# STM32CC.net
KiCad netlist of a schematic drawn in Altium Designer
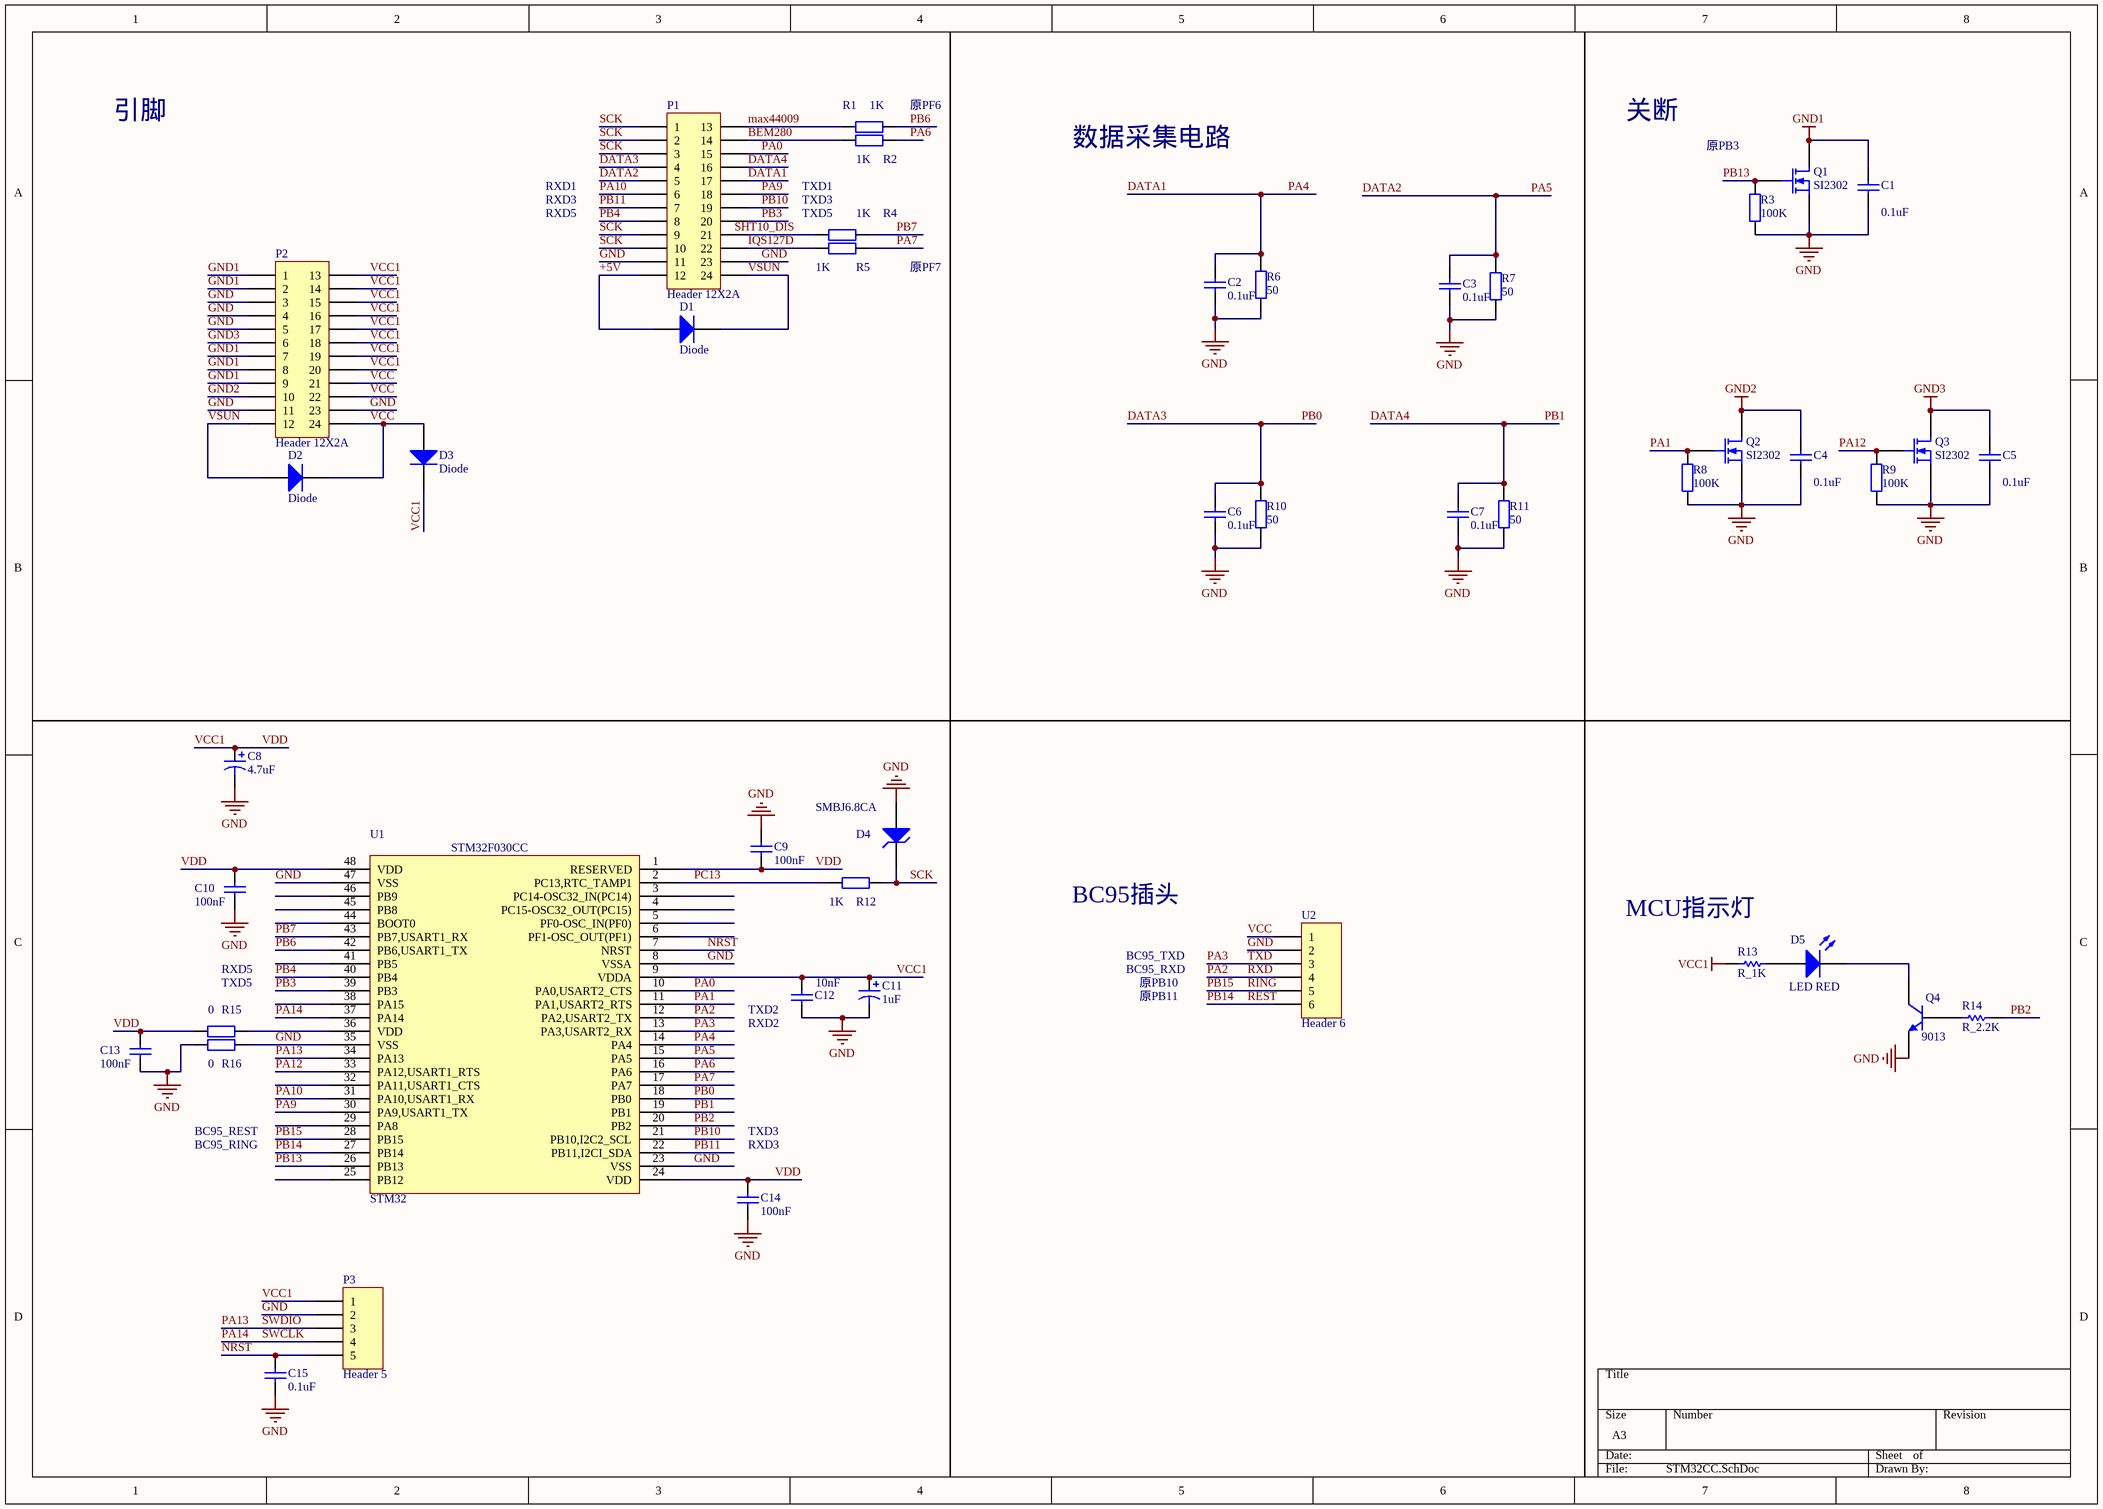
[diagram p0: STM32CC.SchDoc]

(export (version "E")
  (design (tool "Eeschema 10.0.6"))
  (components
    (comp (ref "C1")
      (value "0.1uF")
      (footprint "0603")
      (description "Capacitor")
      (fields (field (name "Comment") "Cap") (field (name "PUBLISHER") "Altium Limited"))
      (libsource (lib "Miscellaneous Devices") (part "Cap"))
    )
    (comp (ref "C2")
      (value "0.1uF")
      (footprint "0603")
      (description "贴片电容 0603")
      (fields (field (name "Comment") "C_0.1uF") (field (name "PUBLISHER") "Altium Limited"))
      (libsource (lib "Miscellaneous Devices") (part "Cap"))
    )
    (comp (ref "C3")
      (value "0.1uF")
      (footprint "0603")
      (description "贴片电容 0603")
      (fields (field (name "Comment") "C_0.1uF") (field (name "PUBLISHER") "Altium Limited"))
      (libsource (lib "Miscellaneous Devices") (part "Cap"))
    )
    (comp (ref "C4")
      (value "0.1uF")
      (footprint "0603")
      (description "Capacitor")
      (fields (field (name "Comment") "Cap") (field (name "PUBLISHER") "Altium Limited"))
      (libsource (lib "Miscellaneous Devices") (part "Cap"))
    )
    (comp (ref "C5")
      (value "0.1uF")
      (footprint "0603")
      (description "Capacitor")
      (fields (field (name "Comment") "Cap") (field (name "PUBLISHER") "Altium Limited"))
      (libsource (lib "Miscellaneous Devices") (part "Cap"))
    )
    (comp (ref "C6")
      (value "0.1uF")
      (footprint "0603")
      (description "贴片电容 0603")
      (fields (field (name "Comment") "C_0.1uF") (field (name "PUBLISHER") "Altium Limited"))
      (libsource (lib "Miscellaneous Devices") (part "Cap"))
    )
    (comp (ref "C7")
      (value "0.1uF")
      (footprint "0603")
      (description "贴片电容 0603")
      (fields (field (name "Comment") "C_0.1uF") (field (name "PUBLISHER") "Altium Limited"))
      (libsource (lib "Miscellaneous Devices") (part "Cap"))
    )
    (comp (ref "C8")
      (value "4.7uF")
      (footprint "1206")
      (description "Polarized Capacitor (Radial)")
      (fields (field (name "PUBLISHER") "Altium Limited"))
      (libsource (lib "Miscellaneous Devices") (part "Cap Pol1"))
    )
    (comp (ref "C9")
      (value "100nF")
      (footprint "0603")
      (description "Capacitor")
      (fields (field (name "PUBLISHER") "Altium Limited"))
      (libsource (lib "Miscellaneous Devices") (part "Cap"))
    )
    (comp (ref "C10")
      (value "100nF")
      (footprint "0603")
      (description "Capacitor")
      (fields (field (name "PUBLISHER") "Altium Limited"))
      (libsource (lib "Miscellaneous Devices") (part "Cap"))
    )
    (comp (ref "C11")
      (value "1uF")
      (footprint "1206")
      (description "Polarized Capacitor (Radial)")
      (fields (field (name "PUBLISHER") "Altium Limited"))
      (libsource (lib "Miscellaneous Devices") (part "Cap Pol1"))
    )
    (comp (ref "C12")
      (value "10nF")
      (footprint "0603")
      (description "Capacitor")
      (fields (field (name "PUBLISHER") "Altium Limited"))
      (libsource (lib "Miscellaneous Devices") (part "Cap"))
    )
    (comp (ref "C13")
      (value "100nF")
      (footprint "0603")
      (description "Capacitor")
      (fields (field (name "PUBLISHER") "Altium Limited"))
      (libsource (lib "Miscellaneous Devices") (part "Cap"))
    )
    (comp (ref "C14")
      (value "100nF")
      (footprint "0603")
      (description "Capacitor")
      (fields (field (name "PUBLISHER") "Altium Limited"))
      (libsource (lib "Miscellaneous Devices") (part "Cap"))
    )
    (comp (ref "C15")
      (value "0.1uF")
      (footprint "0603")
      (description "Capacitor")
      (fields (field (name "PUBLISHER") "Altium Limited"))
      (libsource (lib "Miscellaneous Devices") (part "Cap"))
    )
    (comp (ref "D1")
      (value "Diode")
      (footprint "1N4007-M7")
      (description "Default Diode")
      (fields (field (name "PUBLISHER") "Altium Limited"))
      (libsource (lib "Miscellaneous Devices") (part "Diode"))
    )
    (comp (ref "D2")
      (value "Diode")
      (footprint "1N4007-M7")
      (description "Default Diode")
      (fields (field (name "PUBLISHER") "Altium Limited"))
      (libsource (lib "Miscellaneous Devices") (part "Diode"))
    )
    (comp (ref "D3")
      (value "Diode")
      (footprint "1N4007-M7")
      (description "Default Diode")
      (fields (field (name "PUBLISHER") "Altium Limited"))
      (libsource (lib "Miscellaneous Devices") (part "Diode"))
    )
    (comp (ref "D4")
      (value "SMBJ6.8CA")
      (footprint "DO-214AB")
      (description "Zener Diode")
      (fields (field (name "PUBLISHER") "Altium Limited"))
      (libsource (lib "Miscellaneous Devices") (part "D Zener"))
    )
    (comp (ref "D5")
      (value "LED RED")
      (footprint "LED-3mm")
      (description "插件 发光二极管 5mm 绿发绿光")
      (fields (field (name "PUBLISHER") "Altium Limited"))
      (libsource (lib "Miscellaneous Devices") (part "LED0"))
    )
    (comp (ref "P1")
      (value "Header 12X2A")
      (footprint "HDR2X12_CEN")
      (description "Header, 12-Pin, Dual row")
      (fields (field (name "PUBLISHER") "Altium Limited"))
      (libsource (lib "Miscellaneous Connectors") (part "Header 12X2A"))
    )
    (comp (ref "P2")
      (value "Header 12X2A")
      (footprint "HDR2X12_CEN")
      (description "Header, 12-Pin, Dual row")
      (fields (field (name "PUBLISHER") "Altium Limited"))
      (libsource (lib "Miscellaneous Connectors") (part "Header 12X2A"))
    )
    (comp (ref "P3")
      (value "Header 5")
      (footprint "HDR1X5")
      (description "Header, 5-Pin")
      (fields (field (name "PUBLISHER") "Altium Limited"))
      (libsource (lib "Miscellaneous Connectors") (part "Header 5"))
    )
    (comp (ref "Q1")
      (value "SI2302")
      (footprint "SOT23-3")
      (description "N-Channel MOSFET")
      (fields (field (name "PUBLISHER") "Altium Limited"))
      (libsource (lib "SCHLIB") (part "MOSFET-N"))
    )
    (comp (ref "Q2")
      (value "SI2302")
      (footprint "SOT23-3")
      (description "N-Channel MOSFET")
      (fields (field (name "PUBLISHER") "Altium Limited"))
      (libsource (lib "SCHLIB") (part "MOSFET-N"))
    )
    (comp (ref "Q3")
      (value "SI2302")
      (footprint "SOT23-3")
      (description "N-Channel MOSFET")
      (fields (field (name "PUBLISHER") "Altium Limited"))
      (libsource (lib "SCHLIB") (part "MOSFET-N"))
    )
    (comp (ref "Q4")
      (value "9013")
      (footprint "SOT-23")
      (description "贴片三极管MMBT5551 SOT-23")
      (fields (field (name "PUBLISHER") "Altium Limited"))
      (libsource (lib "MyMiscellaneousDevices") (part "NPN"))
    )
    (comp (ref "R1")
      (value "1K")
      (footprint "0603")
      (description "Resistor")
      (fields (field (name "PUBLISHER") "Altium Limited"))
      (libsource (lib "Miscellaneous Devices") (part "Res2"))
    )
    (comp (ref "R2")
      (value "1K")
      (footprint "0603")
      (description "Resistor")
      (fields (field (name "PUBLISHER") "Altium Limited"))
      (libsource (lib "Miscellaneous Devices") (part "Res2"))
    )
    (comp (ref "R3")
      (value "100K")
      (footprint "0603")
      (description "Resistor")
      (fields (field (name "PUBLISHER") "Altium Limited"))
      (libsource (lib "") (part "Res2_1"))
    )
    (comp (ref "R4")
      (value "1K")
      (footprint "0603")
      (description "Resistor")
      (fields (field (name "PUBLISHER") "Altium Limited"))
      (libsource (lib "Miscellaneous Devices") (part "Res2"))
    )
    (comp (ref "R5")
      (value "1K")
      (footprint "0603")
      (description "Resistor")
      (fields (field (name "PUBLISHER") "Altium Limited"))
      (libsource (lib "Miscellaneous Devices") (part "Res2"))
    )
    (comp (ref "R6")
      (value "50")
      (footprint "0805")
      (description "贴片电阻 0805 精度0.1%")
      (fields (field (name "Comment") "50R") (field (name "PUBLISHER") "Altium Limited"))
      (libsource (lib "") (part "Res2_1"))
    )
    (comp (ref "R7")
      (value "50")
      (footprint "0805")
      (description "贴片电阻 0805 精度0.1%")
      (fields (field (name "Comment") "50R") (field (name "PUBLISHER") "Altium Limited"))
      (libsource (lib "") (part "Res2_1"))
    )
    (comp (ref "R8")
      (value "100K")
      (footprint "0603")
      (description "Resistor")
      (fields (field (name "PUBLISHER") "Altium Limited"))
      (libsource (lib "") (part "Res2_1"))
    )
    (comp (ref "R9")
      (value "100K")
      (footprint "0603")
      (description "Resistor")
      (fields (field (name "PUBLISHER") "Altium Limited"))
      (libsource (lib "") (part "Res2_1"))
    )
    (comp (ref "R10")
      (value "50")
      (footprint "0805")
      (description "贴片电阻 0805 精度0.1%")
      (fields (field (name "Comment") "50R") (field (name "PUBLISHER") "Altium Limited"))
      (libsource (lib "") (part "Res2_1"))
    )
    (comp (ref "R11")
      (value "50")
      (footprint "0805")
      (description "贴片电阻 0805 精度0.1%")
      (fields (field (name "Comment") "50R") (field (name "PUBLISHER") "Altium Limited"))
      (libsource (lib "") (part "Res2_1"))
    )
    (comp (ref "R12")
      (value "1K")
      (footprint "0603")
      (description "Resistor")
      (fields (field (name "PUBLISHER") "Altium Limited"))
      (libsource (lib "Miscellaneous Devices") (part "Res2"))
    )
    (comp (ref "R13")
      (value "R_1K")
      (footprint "0603")
      (description "Resistor")
      (libsource (lib "MyMiscellaneousDevices") (part "Resistor"))
    )
    (comp (ref "R14")
      (value "R_2.2K")
      (footprint "0603")
      (description "Resistor")
      (libsource (lib "MyMiscellaneousDevices") (part "Resistor"))
    )
    (comp (ref "R15")
      (value "0")
      (footprint "0603")
      (description "Resistor")
      (fields (field (name "PUBLISHER") "Altium Limited"))
      (libsource (lib "Miscellaneous Devices") (part "Res2"))
    )
    (comp (ref "R16")
      (value "0")
      (footprint "0603")
      (description "Resistor")
      (fields (field (name "PUBLISHER") "Altium Limited"))
      (libsource (lib "Miscellaneous Devices") (part "Res2"))
    )
    (comp (ref "U1") (value "STM32") (footprint "LQFP48_N") (libsource (lib "STM32F030CC") (part "STM32")))
    (comp (ref "U2")
      (value "Header 6")
      (footprint "PCBComponent_1")
      (description "Header, 6-Pin")
      (fields (field (name "PUBLISHER") "Altium Limited"))
      (libsource (lib "Miscellaneous Connectors") (part "Header 6"))
    )
  )
  (nets
    (net (code "1") (name "/+5V") (class "Default")
      (node (ref "D1") (pin "1") (pinfunction "A_1") (pintype "passive"))
      (node (ref "P1") (pin "12") (pinfunction "12_12") (pintype "passive"))
    )
    (net (code "2") (name "/BEM280") (class "Default")
      (node (ref "P1") (pin "14") (pinfunction "14_14") (pintype "passive"))
      (node (ref "R2") (pin "1") (pinfunction "1_1") (pintype "passive"))
    )
    (net (code "3") (name "/DATA1") (class "Default")
      (node (ref "C2") (pin "1") (pinfunction "1_1") (pintype "passive"))
      (node (ref "P1") (pin "17") (pinfunction "17_17") (pintype "passive"))
      (node (ref "R6") (pin "2") (pinfunction "2_2") (pintype "passive"))
      (node (ref "U1") (pin "14") (pinfunction "PA4_14") (pintype "passive"))
    )
    (net (code "4") (name "/DATA2") (class "Default")
      (node (ref "C3") (pin "1") (pinfunction "1_1") (pintype "passive"))
      (node (ref "P1") (pin "5") (pinfunction "5_5") (pintype "passive"))
      (node (ref "R7") (pin "2") (pinfunction "2_2") (pintype "passive"))
      (node (ref "U1") (pin "15") (pinfunction "PA5_15") (pintype "passive"))
    )
    (net (code "5") (name "/DATA3") (class "Default")
      (node (ref "C6") (pin "1") (pinfunction "1_1") (pintype "passive"))
      (node (ref "P1") (pin "4") (pinfunction "4_4") (pintype "passive"))
      (node (ref "R10") (pin "2") (pinfunction "2_2") (pintype "passive"))
      (node (ref "U1") (pin "18") (pinfunction "PB0_18") (pintype "passive"))
    )
    (net (code "6") (name "/DATA4") (class "Default")
      (node (ref "C7") (pin "1") (pinfunction "1_1") (pintype "passive"))
      (node (ref "P1") (pin "16") (pinfunction "16_16") (pintype "passive"))
      (node (ref "R11") (pin "2") (pinfunction "2_2") (pintype "passive"))
      (node (ref "U1") (pin "19") (pinfunction "PB1_19") (pintype "passive"))
    )
    (net (code "7") (name "/IQS127D") (class "Default")
      (node (ref "P1") (pin "22") (pinfunction "22_22") (pintype "passive"))
      (node (ref "R5") (pin "1") (pinfunction "1_1") (pintype "passive"))
    )
    (net (code "8") (name "/NRST") (class "Default")
      (node (ref "C15") (pin "1") (pinfunction "1_1") (pintype "passive"))
      (node (ref "P3") (pin "5") (pinfunction "5_5") (pintype "passive"))
      (node (ref "U1") (pin "7") (pinfunction "NRST_7") (pintype "passive"))
    )
    (net (code "9") (name "/PA0") (class "Default")
      (node (ref "P1") (pin "15") (pinfunction "15_15") (pintype "passive"))
      (node (ref "U1") (pin "10") (pinfunction "PA0,USART2_CTS_10") (pintype "passive"))
    )
    (net (code "10") (name "/PA1") (class "Default")
      (node (ref "Q2") (pin "1") (pinfunction "G_1") (pintype "passive"))
      (node (ref "R8") (pin "2") (pinfunction "2_2") (pintype "passive"))
      (node (ref "U1") (pin "11") (pinfunction "PA1,USART2_RTS_11") (pintype "passive"))
    )
    (net (code "11") (name "/PA2") (class "Default")
      (node (ref "U1") (pin "12") (pinfunction "PA2,USART2_TX_12") (pintype "passive"))
      (node (ref "U2") (pin "4") (pinfunction "4_4") (pintype "passive"))
    )
    (net (code "12") (name "/PA3") (class "Default")
      (node (ref "U1") (pin "13") (pinfunction "PA3,USART2_RX_13") (pintype "passive"))
      (node (ref "U2") (pin "3") (pinfunction "3_3") (pintype "passive"))
    )
    (net (code "13") (name "/PA6") (class "Default")
      (node (ref "R2") (pin "2") (pinfunction "2_2") (pintype "passive"))
      (node (ref "U1") (pin "16") (pinfunction "PA6_16") (pintype "passive"))
    )
    (net (code "14") (name "/PA7") (class "Default")
      (node (ref "R5") (pin "2") (pinfunction "2_2") (pintype "passive"))
      (node (ref "U1") (pin "17") (pinfunction "PA7_17") (pintype "passive"))
    )
    (net (code "15") (name "/PA9") (class "Default")
      (node (ref "P1") (pin "18") (pinfunction "18_18") (pintype "passive"))
      (node (ref "U1") (pin "30") (pinfunction "PA9,USART1_TX_30") (pintype "passive"))
    )
    (net (code "16") (name "/PA10") (class "Default")
      (node (ref "P1") (pin "6") (pinfunction "6_6") (pintype "passive"))
      (node (ref "U1") (pin "31") (pinfunction "PA10,USART1_RX_31") (pintype "passive"))
    )
    (net (code "17") (name "/PA12") (class "Default")
      (node (ref "Q3") (pin "1") (pinfunction "G_1") (pintype "passive"))
      (node (ref "R9") (pin "2") (pinfunction "2_2") (pintype "passive"))
      (node (ref "U1") (pin "33") (pinfunction "PA12,USART1_RTS_33") (pintype "passive"))
    )
    (net (code "18") (name "/PA13") (class "Default")
      (node (ref "P3") (pin "3") (pinfunction "3_3") (pintype "passive"))
      (node (ref "U1") (pin "34") (pinfunction "PA13_34") (pintype "passive"))
    )
    (net (code "19") (name "/PA14") (class "Default")
      (node (ref "P3") (pin "4") (pinfunction "4_4") (pintype "passive"))
      (node (ref "U1") (pin "37") (pinfunction "PA14_37") (pintype "passive"))
    )
    (net (code "20") (name "/PB2") (class "Default")
      (node (ref "R14") (pin "2") (pinfunction "2_2") (pintype "passive"))
      (node (ref "U1") (pin "20") (pinfunction "PB2_20") (pintype "passive"))
    )
    (net (code "21") (name "/PB3") (class "Default")
      (node (ref "P1") (pin "20") (pinfunction "20_20") (pintype "passive"))
      (node (ref "U1") (pin "39") (pinfunction "PB3_39") (pintype "passive"))
    )
    (net (code "22") (name "/PB4") (class "Default")
      (node (ref "P1") (pin "8") (pinfunction "8_8") (pintype "passive"))
      (node (ref "U1") (pin "40") (pinfunction "PB4_40") (pintype "passive"))
    )
    (net (code "23") (name "/PB6") (class "Default")
      (node (ref "R1") (pin "2") (pinfunction "2_2") (pintype "passive"))
      (node (ref "U1") (pin "42") (pinfunction "PB6,USART1_TX_42") (pintype "passive"))
    )
    (net (code "24") (name "/PB7") (class "Default")
      (node (ref "R4") (pin "2") (pinfunction "2_2") (pintype "passive"))
      (node (ref "U1") (pin "43") (pinfunction "PB7,USART1_RX_43") (pintype "passive"))
    )
    (net (code "25") (name "/PB10") (class "Default")
      (node (ref "P1") (pin "19") (pinfunction "19_19") (pintype "passive"))
      (node (ref "U1") (pin "21") (pinfunction "PB10,I2C2_SCL_21") (pintype "passive"))
    )
    (net (code "26") (name "/PB11") (class "Default")
      (node (ref "P1") (pin "7") (pinfunction "7_7") (pintype "passive"))
      (node (ref "U1") (pin "22") (pinfunction "PB11,I2CI_SDA_22") (pintype "passive"))
    )
    (net (code "27") (name "/PB13") (class "Default")
      (node (ref "Q1") (pin "1") (pinfunction "G_1") (pintype "passive"))
      (node (ref "R3") (pin "2") (pinfunction "2_2") (pintype "passive"))
      (node (ref "U1") (pin "26") (pinfunction "PB13_26") (pintype "passive"))
    )
    (net (code "28") (name "/PB14") (class "Default")
      (node (ref "U1") (pin "27") (pinfunction "PB14_27") (pintype "passive"))
      (node (ref "U2") (pin "6") (pinfunction "6_6") (pintype "passive"))
    )
    (net (code "29") (name "/PB15") (class "Default")
      (node (ref "U1") (pin "28") (pinfunction "PB15_28") (pintype "passive"))
      (node (ref "U2") (pin "5") (pinfunction "5_5") (pintype "passive"))
    )
    (net (code "30") (name "/PC13") (class "Default")
      (node (ref "R12") (pin "1") (pinfunction "1_1") (pintype "passive"))
      (node (ref "U1") (pin "2") (pinfunction "PC13,RTC_TAMP1_2") (pintype "passive"))
    )
    (net (code "31") (name "/SCK") (class "Default")
      (node (ref "D4") (pin "2") (pinfunction "K_2") (pintype "passive"))
      (node (ref "P1") (pin "1") (pinfunction "1_1") (pintype "passive"))
      (node (ref "P1") (pin "10") (pinfunction "10_10") (pintype "passive"))
      (node (ref "P1") (pin "2") (pinfunction "2_2") (pintype "passive"))
      (node (ref "P1") (pin "3") (pinfunction "3_3") (pintype "passive"))
      (node (ref "P1") (pin "9") (pinfunction "9_9") (pintype "passive"))
      (node (ref "R12") (pin "2") (pinfunction "2_2") (pintype "passive"))
    )
    (net (code "33") (name "/VCC") (class "Default")
      (node (ref "D2") (pin "2") (pinfunction "K_2") (pintype "passive"))
      (node (ref "D3") (pin "1") (pinfunction "A_1") (pintype "passive"))
      (node (ref "P2") (pin "21") (pinfunction "21_21") (pintype "passive"))
      (node (ref "P2") (pin "22") (pinfunction "22_22") (pintype "passive"))
      (node (ref "P2") (pin "24") (pinfunction "24_24") (pintype "passive"))
      (node (ref "U2") (pin "1") (pinfunction "1_1") (pintype "passive"))
    )
    (net (code "34") (name "/VSUN") (class "Default")
      (node (ref "D1") (pin "2") (pinfunction "K_2") (pintype "passive"))
      (node (ref "D2") (pin "1") (pinfunction "A_1") (pintype "passive"))
      (node (ref "P1") (pin "24") (pinfunction "24_24") (pintype "passive"))
      (node (ref "P2") (pin "12") (pinfunction "12_12") (pintype "passive"))
    )
    (net (code "35") (name "/max44009") (class "Default")
      (node (ref "P1") (pin "13") (pinfunction "13_13") (pintype "passive"))
      (node (ref "R1") (pin "1") (pinfunction "1_1") (pintype "passive"))
    )
    (net (code "36") (name "GND") (class "Default")
      (node (ref "C1") (pin "1") (pinfunction "1_1") (pintype "passive"))
      (node (ref "C10") (pin "1") (pinfunction "1_1") (pintype "passive"))
      (node (ref "C11") (pin "2") (pinfunction "2_2") (pintype "passive"))
      (node (ref "C12") (pin "1") (pinfunction "1_1") (pintype "passive"))
      (node (ref "C13") (pin "1") (pinfunction "1_1") (pintype "passive"))
      (node (ref "C14") (pin "1") (pinfunction "1_1") (pintype "passive"))
      (node (ref "C15") (pin "2") (pinfunction "2_2") (pintype "passive"))
      (node (ref "C2") (pin "2") (pinfunction "2_2") (pintype "passive"))
      (node (ref "C3") (pin "2") (pinfunction "2_2") (pintype "passive"))
      (node (ref "C4") (pin "1") (pinfunction "1_1") (pintype "passive"))
      (node (ref "C5") (pin "1") (pinfunction "1_1") (pintype "passive"))
      (node (ref "C6") (pin "2") (pinfunction "2_2") (pintype "passive"))
      (node (ref "C7") (pin "2") (pinfunction "2_2") (pintype "passive"))
      (node (ref "C8") (pin "2") (pinfunction "2_2") (pintype "passive"))
      (node (ref "C9") (pin "2") (pinfunction "2_2") (pintype "passive"))
      (node (ref "D4") (pin "1") (pinfunction "A_1") (pintype "passive"))
      (node (ref "P1") (pin "11") (pinfunction "11_11") (pintype "passive"))
      (node (ref "P1") (pin "23") (pinfunction "23_23") (pintype "passive"))
      (node (ref "P2") (pin "11") (pinfunction "11_11") (pintype "passive"))
      (node (ref "P2") (pin "23") (pinfunction "23_23") (pintype "passive"))
      (node (ref "P2") (pin "3") (pinfunction "3_3") (pintype "passive"))
      (node (ref "P2") (pin "4") (pinfunction "4_4") (pintype "passive"))
      (node (ref "P2") (pin "5") (pinfunction "5_5") (pintype "passive"))
      (node (ref "P3") (pin "2") (pinfunction "2_2") (pintype "passive"))
      (node (ref "Q1") (pin "2") (pinfunction "S_2") (pintype "passive"))
      (node (ref "Q2") (pin "2") (pinfunction "S_2") (pintype "passive"))
      (node (ref "Q3") (pin "2") (pinfunction "S_2") (pintype "passive"))
      (node (ref "Q4") (pin "2") (pinfunction "E_2") (pintype "passive"))
      (node (ref "R10") (pin "1") (pinfunction "1_1") (pintype "passive"))
      (node (ref "R11") (pin "1") (pinfunction "1_1") (pintype "passive"))
      (node (ref "R16") (pin "1") (pinfunction "1_1") (pintype "passive"))
      (node (ref "R16") (pin "2") (pinfunction "2_2") (pintype "passive"))
      (node (ref "R3") (pin "1") (pinfunction "1_1") (pintype "passive"))
      (node (ref "R6") (pin "1") (pinfunction "1_1") (pintype "passive"))
      (node (ref "R7") (pin "1") (pinfunction "1_1") (pintype "passive"))
      (node (ref "R8") (pin "1") (pinfunction "1_1") (pintype "passive"))
      (node (ref "R9") (pin "1") (pinfunction "1_1") (pintype "passive"))
      (node (ref "U1") (pin "23") (pinfunction "VSS_23") (pintype "passive"))
      (node (ref "U1") (pin "35") (pinfunction "VSS_35") (pintype "passive"))
      (node (ref "U1") (pin "47") (pinfunction "VSS_47") (pintype "passive"))
      (node (ref "U1") (pin "8") (pinfunction "VSSA_8") (pintype "passive"))
      (node (ref "U2") (pin "2") (pinfunction "2_2") (pintype "passive"))
    )
    (net (code "37") (name "GND1") (class "Default")
      (node (ref "C1") (pin "2") (pinfunction "2_2") (pintype "passive"))
      (node (ref "P2") (pin "1") (pinfunction "1_1") (pintype "passive"))
      (node (ref "P2") (pin "2") (pinfunction "2_2") (pintype "passive"))
      (node (ref "P2") (pin "7") (pinfunction "7_7") (pintype "passive"))
      (node (ref "P2") (pin "8") (pinfunction "8_8") (pintype "passive"))
      (node (ref "P2") (pin "9") (pinfunction "9_9") (pintype "passive"))
      (node (ref "Q1") (pin "3") (pinfunction "D_3") (pintype "passive"))
    )
    (net (code "38") (name "GND2") (class "Default")
      (node (ref "C4") (pin "2") (pinfunction "2_2") (pintype "passive"))
      (node (ref "P2") (pin "10") (pinfunction "10_10") (pintype "passive"))
      (node (ref "Q2") (pin "3") (pinfunction "D_3") (pintype "passive"))
    )
    (net (code "39") (name "GND3") (class "Default")
      (node (ref "C5") (pin "2") (pinfunction "2_2") (pintype "passive"))
      (node (ref "P2") (pin "6") (pinfunction "6_6") (pintype "passive"))
      (node (ref "Q3") (pin "3") (pinfunction "D_3") (pintype "passive"))
    )
    (net (code "40") (name "Net-(D5-A)") (class "Default")
      (node (ref "D5") (pin "1") (pinfunction "A_1") (pintype "passive"))
      (node (ref "R13") (pin "2") (pinfunction "2_2") (pintype "passive"))
    )
    (net (code "41") (name "Net-(D5-K)") (class "Default")
      (node (ref "D5") (pin "2") (pinfunction "K_2") (pintype "passive"))
      (node (ref "Q4") (pin "3") (pinfunction "C_3") (pintype "passive"))
    )
    (net (code "42") (name "Net-(P1-Pad21)") (class "Default")
      (node (ref "P1") (pin "21") (pinfunction "21_21") (pintype "passive"))
      (node (ref "R4") (pin "1") (pinfunction "1_1") (pintype "passive"))
    )
    (net (code "43") (name "Net-(Q4-B)") (class "Default")
      (node (ref "Q4") (pin "1") (pinfunction "B_1") (pintype "passive"))
      (node (ref "R14") (pin "1") (pinfunction "1_1") (pintype "passive"))
    )
    (net (code "44") (name "Net-(R15-Pad2)") (class "Default")
      (node (ref "R15") (pin "2") (pinfunction "2_2") (pintype "passive"))
      (node (ref "U1") (pin "36") (pinfunction "VDD_36") (pintype "passive"))
    )
    (net (code "45") (name "VCC1") (class "Default")
      (node (ref "C10") (pin "2") (pinfunction "2_2") (pintype "passive"))
      (node (ref "C11") (pin "1") (pinfunction "1_1") (pintype "passive"))
      (node (ref "C12") (pin "2") (pinfunction "2_2") (pintype "passive"))
      (node (ref "C13") (pin "2") (pinfunction "2_2") (pintype "passive"))
      (node (ref "C14") (pin "2") (pinfunction "2_2") (pintype "passive"))
      (node (ref "C8") (pin "1") (pinfunction "1_1") (pintype "passive"))
      (node (ref "C9") (pin "1") (pinfunction "1_1") (pintype "passive"))
      (node (ref "D3") (pin "2") (pinfunction "K_2") (pintype "passive"))
      (node (ref "P2") (pin "13") (pinfunction "13_13") (pintype "passive"))
      (node (ref "P2") (pin "14") (pinfunction "14_14") (pintype "passive"))
      (node (ref "P2") (pin "15") (pinfunction "15_15") (pintype "passive"))
      (node (ref "P2") (pin "16") (pinfunction "16_16") (pintype "passive"))
      (node (ref "P2") (pin "17") (pinfunction "17_17") (pintype "passive"))
      (node (ref "P2") (pin "18") (pinfunction "18_18") (pintype "passive"))
      (node (ref "P2") (pin "19") (pinfunction "19_19") (pintype "passive"))
      (node (ref "P2") (pin "20") (pinfunction "20_20") (pintype "passive"))
      (node (ref "P3") (pin "1") (pinfunction "1_1") (pintype "passive"))
      (node (ref "R13") (pin "1") (pinfunction "1_1") (pintype "passive"))
      (node (ref "R15") (pin "1") (pinfunction "1_1") (pintype "passive"))
      (node (ref "U1") (pin "1") (pinfunction "RESERVED_1") (pintype "passive"))
      (node (ref "U1") (pin "24") (pinfunction "VDD_24") (pintype "passive"))
      (node (ref "U1") (pin "48") (pinfunction "VDD_48") (pintype "passive"))
      (node (ref "U1") (pin "9") (pinfunction "VDDA_9") (pintype "passive"))
    )
    (net (code "46") (name "unconnected-(U1-BOOT0-Pad44)") (class "Default")
      (node (ref "U1") (pin "44") (pinfunction "BOOT0_44") (pintype "passive"))
    )
    (net (code "47") (name "unconnected-(U1-PA8-Pad29)") (class "Default")
      (node (ref "U1") (pin "29") (pinfunction "PA8_29") (pintype "passive"))
    )
    (net (code "48") (name "unconnected-(U1-PA11,USART1_CTS-Pad32)") (class "Default")
      (node (ref "U1") (pin "32") (pinfunction "PA11,USART1_CTS_32") (pintype "passive"))
    )
    (net (code "49") (name "unconnected-(U1-PA15-Pad38)") (class "Default")
      (node (ref "U1") (pin "38") (pinfunction "PA15_38") (pintype "passive"))
    )
    (net (code "50") (name "unconnected-(U1-PB5-Pad41)") (class "Default")
      (node (ref "U1") (pin "41") (pinfunction "PB5_41") (pintype "passive"))
    )
    (net (code "51") (name "unconnected-(U1-PB8-Pad45)") (class "Default")
      (node (ref "U1") (pin "45") (pinfunction "PB8_45") (pintype "passive"))
    )
    (net (code "52") (name "unconnected-(U1-PB9-Pad46)") (class "Default")
      (node (ref "U1") (pin "46") (pinfunction "PB9_46") (pintype "passive"))
    )
    (net (code "53") (name "unconnected-(U1-PB12-Pad25)") (class "Default")
      (node (ref "U1") (pin "25") (pinfunction "PB12_25") (pintype "passive"))
    )
    (net (code "54") (name "unconnected-(U1-PC14-OSC32_IN(PC14)-Pad3)") (class "Default")
      (node (ref "U1") (pin "3") (pinfunction "PC14-OSC32_IN(PC14)_3") (pintype "passive"))
    )
    (net (code "55") (name "unconnected-(U1-PC15-OSC32_OUT(PC15)-Pad4)") (class "Default")
      (node (ref "U1") (pin "4") (pinfunction "PC15-OSC32_OUT(PC15)_4") (pintype "passive"))
    )
    (net (code "56") (name "unconnected-(U1-PF0-OSC_IN(PF0)-Pad5)") (class "Default")
      (node (ref "U1") (pin "5") (pinfunction "PF0-OSC_IN(PF0)_5") (pintype "passive"))
    )
    (net (code "57") (name "unconnected-(U1-PF1-OSC_OUT(PF1)-Pad6)") (class "Default")
      (node (ref "U1") (pin "6") (pinfunction "PF1-OSC_OUT(PF1)_6") (pintype "passive"))
    )
  )
)
